# 04_Input_Output.net
KiCad netlist of a schematic drawn in Altium Designer
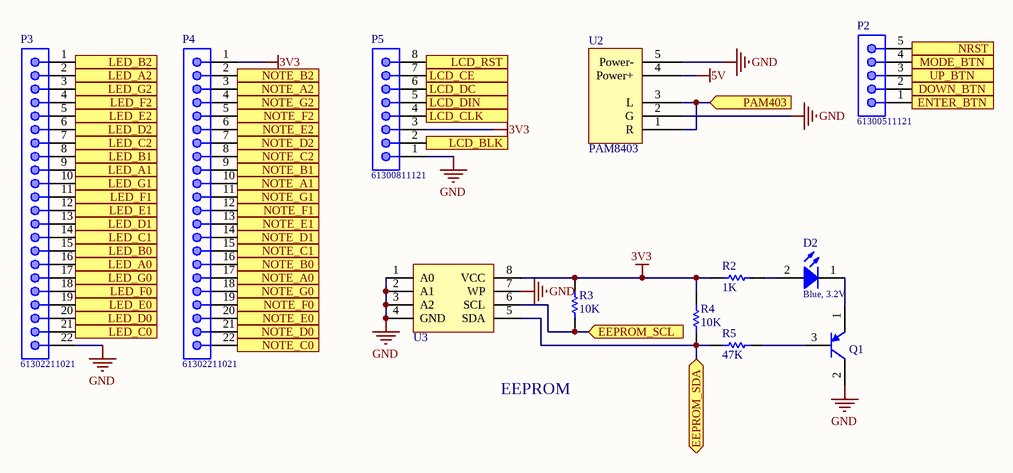
[diagram p0: 04_Input_Output.SchDoc]

(export (version "E")
  (design (tool "Eeschema 10.0.6"))
  (components
    (comp (ref "D2")
      (value "Blue, 3.2V")
      (footprint "WL-SMCW_0603 dome")
      (description "WL-SMCW SMT Mono-color Chip LED Waterclear, size 0603 dome, Blue, 3.2V, 40deg")
      (fields (field (name "PART NUMBER") "150060BS84000") (field (name "PUBLISHER") "Wurth Elektronik"))
      (libsource (lib "Altium_WL-SMCW (rev20a)") (part "150060BS84000"))
    )
    (comp (ref "P2")
      (value "61300511121")
      (footprint "61300511121")
      (description "WR-PHD Pin Header, THT, pitch 2.54mm, Single Row, Vertical, 5p")
      (fields (field (name "MANUFACTURER") "Wurth Elektronik"))
      (libsource (lib "Altium_WR-PHD (rev20a)") (part "61300511121"))
    )
    (comp (ref "P3")
      (value "61302211021")
      (footprint "61302211021")
      (description "WR-PHD Pin Header, THT, pitch 2.54mm, Single Row, Angled, 22p")
      (fields (field (name "MANUFACTURER") "Wurth Elektronik"))
      (libsource (lib "Altium_WR-PHD (rev20a)") (part "61302211021"))
    )
    (comp (ref "P4")
      (value "61302211021")
      (footprint "61302211021")
      (description "WR-PHD Pin Header, THT, pitch 2.54mm, Single Row, Angled, 22p")
      (fields (field (name "MANUFACTURER") "Wurth Elektronik"))
      (libsource (lib "Altium_WR-PHD (rev20a)") (part "61302211021"))
    )
    (comp (ref "P5")
      (value "61300811121")
      (footprint "61300811121")
      (description "WR-PHD Pin Header, THT, pitch 2.54mm, Single Row, Vertical, 8p")
      (fields (field (name "MANUFACTURER") "Wurth Elektronik"))
      (libsource (lib "Altium_WR-PHD (rev20a)") (part "61300811121"))
    )
    (comp (ref "Q1")
      (value "A1015")
      (footprint "SOT23B")
      (description "PNP Bipolar Transistor")
      (libsource (lib "PIF_Library") (part "A1015"))
    )
    (comp (ref "R2")
      (value "1K")
      (footprint "RES-SM-0603")
      (description "Resistor")
      (fields (field (name "Comment") "RESISTOR SMD"))
      (libsource (lib "PIF_Library") (part "RESISTOR SMD"))
    )
    (comp (ref "R3")
      (value "10K")
      (footprint "RES-SM-0603")
      (description "Resistor")
      (fields (field (name "Comment") "RESISTOR SMD"))
      (libsource (lib "PIF_Library") (part "RESISTOR SMD"))
    )
    (comp (ref "R4")
      (value "10K")
      (footprint "RES-SM-0603")
      (description "Resistor")
      (fields (field (name "Comment") "RESISTOR SMD"))
      (libsource (lib "PIF_Library") (part "RESISTOR SMD"))
    )
    (comp (ref "R5")
      (value "47K")
      (footprint "RES-SM-0603")
      (description "Resistor")
      (fields (field (name "Comment") "RESISTOR SMD"))
      (libsource (lib "PIF_Library") (part "RESISTOR SMD"))
    )
    (comp (ref "U2") (value "PAM8403") (footprint "PAM8403") (libsource (lib "YenDoo") (part "PAM8403")))
    (comp (ref "U3")
      (value "24C256")
      (footprint "SOIC-8")
      (description "EEPROM Memory IC 256Kb (32K x 8) I²C 1 MHz 550 ns 8-SOIC")
      (fields (field (name "MFR") "Microchip Technology"))
      (libsource (lib "YenDoo") (part "24C256"))
    )
  )
  (nets
    (net (code "1") (name "/DOWN_BTN") (class "Default")
      (node (ref "P2") (pin "2") (pinfunction "2_2") (pintype "passive"))
    )
    (net (code "2") (name "/EEPROM_SCL") (class "Default")
      (node (ref "R3") (pin "1") (pinfunction "1_1") (pintype "passive"))
      (node (ref "U3") (pin "6") (pinfunction "SCL_6") (pintype "passive"))
    )
    (net (code "3") (name "/EEPROM_SDA") (class "Default")
      (node (ref "R4") (pin "1") (pinfunction "1_1") (pintype "passive"))
      (node (ref "R5") (pin "2") (pinfunction "2_2") (pintype "passive"))
      (node (ref "U3") (pin "5") (pinfunction "SDA_5") (pintype "passive"))
    )
    (net (code "4") (name "/ENTER_BTN") (class "Default")
      (node (ref "P2") (pin "1") (pinfunction "1_1") (pintype "passive"))
    )
    (net (code "5") (name "/LCD_BLK") (class "Default")
      (node (ref "P5") (pin "2") (pinfunction "2_2") (pintype "passive"))
    )
    (net (code "6") (name "/LCD_CE") (class "Default")
      (node (ref "P5") (pin "7") (pinfunction "7_7") (pintype "passive"))
    )
    (net (code "7") (name "/LCD_CLK") (class "Default")
      (node (ref "P5") (pin "4") (pinfunction "4_4") (pintype "passive"))
    )
    (net (code "8") (name "/LCD_DC") (class "Default")
      (node (ref "P5") (pin "6") (pinfunction "6_6") (pintype "passive"))
    )
    (net (code "9") (name "/LCD_DIN") (class "Default")
      (node (ref "P5") (pin "5") (pinfunction "5_5") (pintype "passive"))
    )
    (net (code "10") (name "/LCD_RST") (class "Default")
      (node (ref "P5") (pin "8") (pinfunction "8_8") (pintype "passive"))
    )
    (net (code "11") (name "/LED_A0") (class "Default")
      (node (ref "P3") (pin "16") (pinfunction "16_16") (pintype "passive"))
    )
    (net (code "12") (name "/LED_A1") (class "Default")
      (node (ref "P3") (pin "9") (pinfunction "9_9") (pintype "passive"))
    )
    (net (code "13") (name "/LED_A2") (class "Default")
      (node (ref "P3") (pin "2") (pinfunction "2_2") (pintype "passive"))
    )
    (net (code "14") (name "/LED_B0") (class "Default")
      (node (ref "P3") (pin "15") (pinfunction "15_15") (pintype "passive"))
    )
    (net (code "15") (name "/LED_B1") (class "Default")
      (node (ref "P3") (pin "8") (pinfunction "8_8") (pintype "passive"))
    )
    (net (code "16") (name "/LED_B2") (class "Default")
      (node (ref "P3") (pin "1") (pinfunction "1_1") (pintype "passive"))
    )
    (net (code "17") (name "/LED_C0") (class "Default")
      (node (ref "P3") (pin "21") (pinfunction "21_21") (pintype "passive"))
    )
    (net (code "18") (name "/LED_C1") (class "Default")
      (node (ref "P3") (pin "14") (pinfunction "14_14") (pintype "passive"))
    )
    (net (code "19") (name "/LED_C2") (class "Default")
      (node (ref "P3") (pin "7") (pinfunction "7_7") (pintype "passive"))
    )
    (net (code "20") (name "/LED_D0") (class "Default")
      (node (ref "P3") (pin "20") (pinfunction "20_20") (pintype "passive"))
    )
    (net (code "21") (name "/LED_D1") (class "Default")
      (node (ref "P3") (pin "13") (pinfunction "13_13") (pintype "passive"))
    )
    (net (code "22") (name "/LED_D2") (class "Default")
      (node (ref "P3") (pin "6") (pinfunction "6_6") (pintype "passive"))
    )
    (net (code "23") (name "/LED_E0") (class "Default")
      (node (ref "P3") (pin "19") (pinfunction "19_19") (pintype "passive"))
    )
    (net (code "24") (name "/LED_E1") (class "Default")
      (node (ref "P3") (pin "12") (pinfunction "12_12") (pintype "passive"))
    )
    (net (code "25") (name "/LED_E2") (class "Default")
      (node (ref "P3") (pin "5") (pinfunction "5_5") (pintype "passive"))
    )
    (net (code "26") (name "/LED_F0") (class "Default")
      (node (ref "P3") (pin "18") (pinfunction "18_18") (pintype "passive"))
    )
    (net (code "27") (name "/LED_F1") (class "Default")
      (node (ref "P3") (pin "11") (pinfunction "11_11") (pintype "passive"))
    )
    (net (code "28") (name "/LED_F2") (class "Default")
      (node (ref "P3") (pin "4") (pinfunction "4_4") (pintype "passive"))
    )
    (net (code "29") (name "/LED_G0") (class "Default")
      (node (ref "P3") (pin "17") (pinfunction "17_17") (pintype "passive"))
    )
    (net (code "30") (name "/LED_G1") (class "Default")
      (node (ref "P3") (pin "10") (pinfunction "10_10") (pintype "passive"))
    )
    (net (code "31") (name "/LED_G2") (class "Default")
      (node (ref "P3") (pin "3") (pinfunction "3_3") (pintype "passive"))
    )
    (net (code "32") (name "/MODE_BTN") (class "Default")
      (node (ref "P2") (pin "4") (pinfunction "4_4") (pintype "passive"))
    )
    (net (code "33") (name "/NOTE_A0") (class "Default")
      (node (ref "P4") (pin "17") (pinfunction "17_17") (pintype "passive"))
    )
    (net (code "34") (name "/NOTE_A1") (class "Default")
      (node (ref "P4") (pin "10") (pinfunction "10_10") (pintype "passive"))
    )
    (net (code "35") (name "/NOTE_A2") (class "Default")
      (node (ref "P4") (pin "3") (pinfunction "3_3") (pintype "passive"))
    )
    (net (code "36") (name "/NOTE_B0") (class "Default")
      (node (ref "P4") (pin "16") (pinfunction "16_16") (pintype "passive"))
    )
    (net (code "37") (name "/NOTE_B1") (class "Default")
      (node (ref "P4") (pin "9") (pinfunction "9_9") (pintype "passive"))
    )
    (net (code "38") (name "/NOTE_B2") (class "Default")
      (node (ref "P4") (pin "2") (pinfunction "2_2") (pintype "passive"))
    )
    (net (code "39") (name "/NOTE_C0") (class "Default")
      (node (ref "P4") (pin "22") (pinfunction "22_22") (pintype "passive"))
    )
    (net (code "40") (name "/NOTE_C1") (class "Default")
      (node (ref "P4") (pin "15") (pinfunction "15_15") (pintype "passive"))
    )
    (net (code "41") (name "/NOTE_C2") (class "Default")
      (node (ref "P4") (pin "8") (pinfunction "8_8") (pintype "passive"))
    )
    (net (code "42") (name "/NOTE_D0") (class "Default")
      (node (ref "P4") (pin "21") (pinfunction "21_21") (pintype "passive"))
    )
    (net (code "43") (name "/NOTE_D1") (class "Default")
      (node (ref "P4") (pin "14") (pinfunction "14_14") (pintype "passive"))
    )
    (net (code "44") (name "/NOTE_D2") (class "Default")
      (node (ref "P4") (pin "7") (pinfunction "7_7") (pintype "passive"))
    )
    (net (code "45") (name "/NOTE_E0") (class "Default")
      (node (ref "P4") (pin "20") (pinfunction "20_20") (pintype "passive"))
    )
    (net (code "46") (name "/NOTE_E1") (class "Default")
      (node (ref "P4") (pin "13") (pinfunction "13_13") (pintype "passive"))
    )
    (net (code "47") (name "/NOTE_E2") (class "Default")
      (node (ref "P4") (pin "6") (pinfunction "6_6") (pintype "passive"))
    )
    (net (code "48") (name "/NOTE_F0") (class "Default")
      (node (ref "P4") (pin "19") (pinfunction "19_19") (pintype "passive"))
    )
    (net (code "49") (name "/NOTE_F1") (class "Default")
      (node (ref "P4") (pin "12") (pinfunction "12_12") (pintype "passive"))
    )
    (net (code "50") (name "/NOTE_F2") (class "Default")
      (node (ref "P4") (pin "5") (pinfunction "5_5") (pintype "passive"))
    )
    (net (code "51") (name "/NOTE_G0") (class "Default")
      (node (ref "P4") (pin "18") (pinfunction "18_18") (pintype "passive"))
    )
    (net (code "52") (name "/NOTE_G1") (class "Default")
      (node (ref "P4") (pin "11") (pinfunction "11_11") (pintype "passive"))
    )
    (net (code "53") (name "/NOTE_G2") (class "Default")
      (node (ref "P4") (pin "4") (pinfunction "4_4") (pintype "passive"))
    )
    (net (code "54") (name "/NRST") (class "Default")
      (node (ref "P2") (pin "5") (pinfunction "5_5") (pintype "passive"))
    )
    (net (code "55") (name "/PAM403") (class "Default")
      (node (ref "U2") (pin "1") (pinfunction "R_1") (pintype "passive"))
      (node (ref "U2") (pin "3") (pinfunction "L_3") (pintype "passive"))
    )
    (net (code "56") (name "/UP_BTN") (class "Default")
      (node (ref "P2") (pin "3") (pinfunction "3_3") (pintype "passive"))
    )
    (net (code "57") (name "3V3") (class "Default")
      (node (ref "P4") (pin "1") (pinfunction "1_1") (pintype "passive"))
      (node (ref "P5") (pin "3") (pinfunction "3_3") (pintype "passive"))
      (node (ref "R2") (pin "2") (pinfunction "2_2") (pintype "passive"))
      (node (ref "R3") (pin "2") (pinfunction "2_2") (pintype "passive"))
      (node (ref "R4") (pin "2") (pinfunction "2_2") (pintype "passive"))
      (node (ref "U3") (pin "8") (pinfunction "VCC_8") (pintype "passive"))
    )
    (net (code "58") (name "5V") (class "Default")
      (node (ref "U2") (pin "4") (pinfunction "Power+_4") (pintype "passive"))
    )
    (net (code "59") (name "GND") (class "Default")
      (node (ref "P3") (pin "22") (pinfunction "22_22") (pintype "passive"))
      (node (ref "P5") (pin "1") (pinfunction "1_1") (pintype "passive"))
      (node (ref "Q1") (pin "2") (pinfunction "C_2") (pintype "passive"))
      (node (ref "U2") (pin "2") (pinfunction "G_2") (pintype "passive"))
      (node (ref "U2") (pin "5") (pinfunction "Power-_5") (pintype "passive"))
      (node (ref "U3") (pin "1") (pinfunction "A0_1") (pintype "passive"))
      (node (ref "U3") (pin "2") (pinfunction "A1_2") (pintype "passive"))
      (node (ref "U3") (pin "3") (pinfunction "A2_3") (pintype "passive"))
      (node (ref "U3") (pin "4") (pinfunction "GND_4") (pintype "passive"))
      (node (ref "U3") (pin "7") (pinfunction "WP_7") (pintype "passive"))
    )
    (net (code "60") (name "Net-(D2-A)") (class "Default")
      (node (ref "D2") (pin "2") (pinfunction "A_2") (pintype "passive"))
      (node (ref "R2") (pin "1") (pinfunction "1_1") (pintype "passive"))
    )
    (net (code "61") (name "Net-(D2-K)") (class "Default")
      (node (ref "D2") (pin "1") (pinfunction "K_1") (pintype "passive"))
      (node (ref "Q1") (pin "1") (pinfunction "E_1") (pintype "passive"))
    )
    (net (code "62") (name "Net-(Q1-B)") (class "Default")
      (node (ref "Q1") (pin "3") (pinfunction "B_3") (pintype "passive"))
      (node (ref "R5") (pin "1") (pinfunction "1_1") (pintype "passive"))
    )
  )
)
